# Prototipo_2X.net
KiCad netlist of a schematic drawn in EAGLE
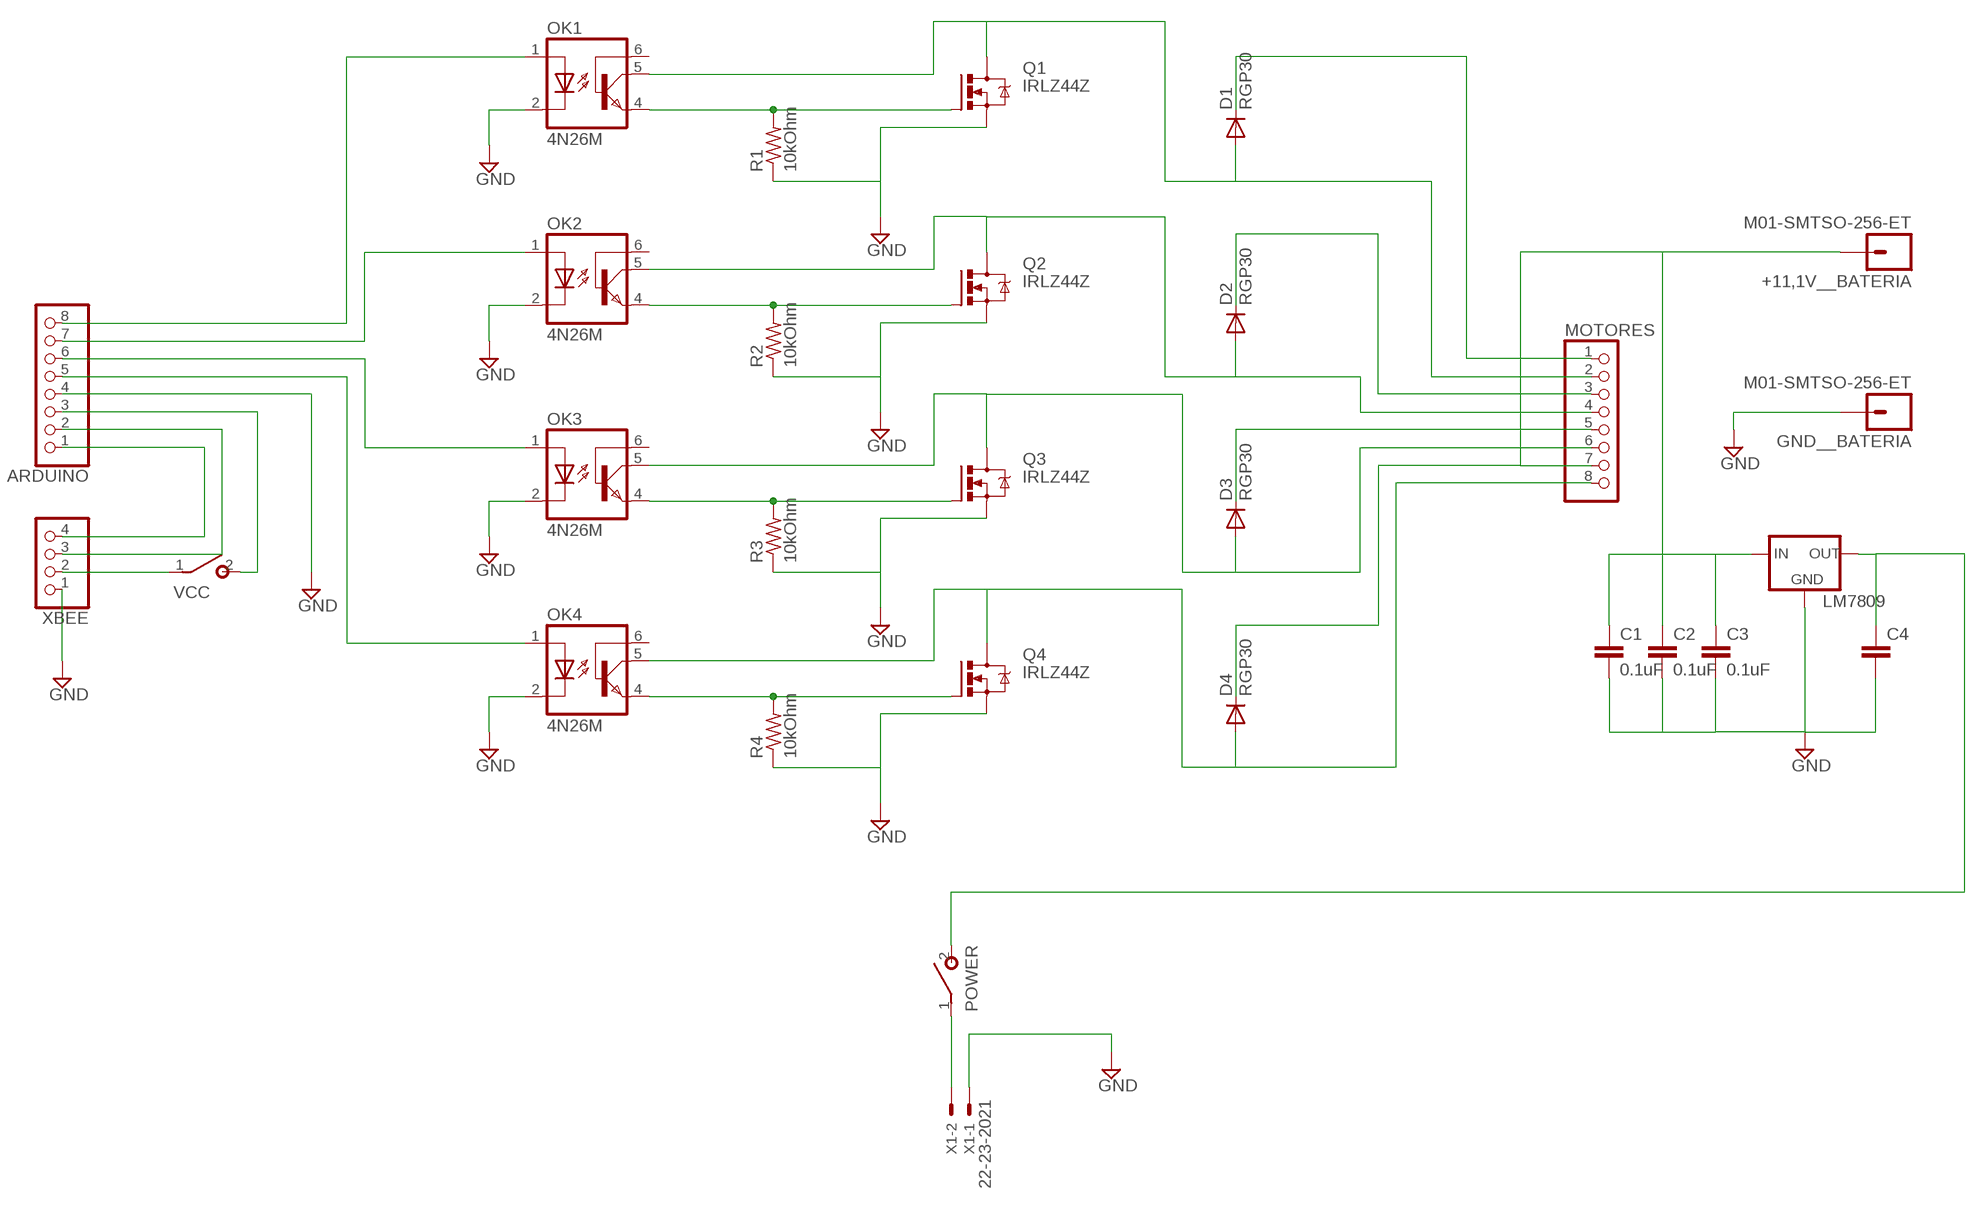
[diagram p0: schematic, sheet 1]

(export (version "E")
  (design (tool "Eeschema 10.0.6"))
  (components
    (comp (ref "+11,1V__BATERIA")
      (value "M01-SMTSO-256-ET")
      (footprint "eagle-import:SMTSO-256-ET")
      (libsource (lib "eagle-import") (part "M01-SMTSO-256-ET"))
    )
    (comp (ref "ARDUINO")
      (value "PINHD-1X8/90")
      (footprint "eagle-import:1X08_90")
      (libsource (lib "eagle-import") (part "PINHD-1X8/90"))
    )
    (comp (ref "C1")
      (value "0.1uF")
      (footprint "eagle-import:CAP-PTH-SMALL-KIT")
      (fields (field (name "PROD_ID") "CAP-08370"))
      (libsource (lib "eagle-import") (part "0.1UF-50V-20%(PTH)KIT-EZ"))
    )
    (comp (ref "C2")
      (value "0.1uF")
      (footprint "eagle-import:CAP-PTH-SMALL-KIT")
      (fields (field (name "PROD_ID") "CAP-08370"))
      (libsource (lib "eagle-import") (part "0.1UF-50V-20%(PTH)KIT-EZ"))
    )
    (comp (ref "C3")
      (value "0.1uF")
      (footprint "eagle-import:CAP-PTH-SMALL-KIT")
      (libsource (lib "eagle-import") (part "0.1UF-50V-20%(PTH)KIT-EZ"))
    )
    (comp (ref "C4")
      (value "0.1UF-50V-20%(PTH)KIT-EZ")
      (footprint "eagle-import:CAP-PTH-SMALL-KIT")
      (fields (field (name "PROD_ID") "CAP-08370"))
      (libsource (lib "eagle-import") (part "0.1UF-50V-20%(PTH)KIT-EZ"))
    )
    (comp (ref "D1")
      (value "RGP30")
      (footprint "eagle-import:DO201-15")
      (libsource (lib "eagle-import") (part "RGP30"))
    )
    (comp (ref "D2")
      (value "RGP30")
      (footprint "eagle-import:DO201-15")
      (libsource (lib "eagle-import") (part "RGP30"))
    )
    (comp (ref "D3")
      (value "RGP30")
      (footprint "eagle-import:DO201-15")
      (libsource (lib "eagle-import") (part "RGP30"))
    )
    (comp (ref "D4")
      (value "RGP30")
      (footprint "eagle-import:DO201-15")
      (libsource (lib "eagle-import") (part "RGP30"))
    )
    (comp (ref "GND__BATERIA")
      (value "M01-SMTSO-256-ET")
      (footprint "eagle-import:SMTSO-256-ET")
      (libsource (lib "eagle-import") (part "M01-SMTSO-256-ET"))
    )
    (comp (ref "LM7809")
      (value "78XXL")
      (footprint "eagle-import:78XXL")
      (libsource (lib "eagle-import") (part "78XXL"))
    )
    (comp (ref "MOTORES")
      (value "PINHD-1X8/90")
      (footprint "eagle-import:1X08_90")
      (libsource (lib "eagle-import") (part "PINHD-1X8/90"))
    )
    (comp (ref "OK1")
      (value "4N26M")
      (footprint "eagle-import:DIL06")
      (fields (field (name "MPN") "4N26-M"))
      (libsource (lib "eagle-import") (part "4N?M26"))
    )
    (comp (ref "OK2")
      (value "4N26M")
      (footprint "eagle-import:DIL06")
      (fields (field (name "MPN") "4N26-M"))
      (libsource (lib "eagle-import") (part "4N?M26"))
    )
    (comp (ref "OK3")
      (value "4N26M")
      (footprint "eagle-import:DIL06")
      (fields (field (name "MPN") "4N26-M"))
      (libsource (lib "eagle-import") (part "4N?M26"))
    )
    (comp (ref "OK4")
      (value "4N26M")
      (footprint "eagle-import:DIL06")
      (fields (field (name "MPN") "4N26-M"))
      (libsource (lib "eagle-import") (part "4N?M26"))
    )
    (comp (ref "POWER")
      (value "SPST")
      (footprint "eagle-import:SPST")
      (libsource (lib "eagle-import") (part "SPST"))
    )
    (comp (ref "Q1")
      (value "IRLZ44Z")
      (footprint "eagle-import:TO220BH")
      (libsource (lib "eagle-import") (part "IRLZ44Z"))
    )
    (comp (ref "Q2")
      (value "IRLZ44Z")
      (footprint "eagle-import:TO220BH")
      (libsource (lib "eagle-import") (part "IRLZ44Z"))
    )
    (comp (ref "Q3")
      (value "IRLZ44Z")
      (footprint "eagle-import:TO220BH")
      (libsource (lib "eagle-import") (part "IRLZ44Z"))
    )
    (comp (ref "Q4")
      (value "IRLZ44Z")
      (footprint "eagle-import:TO220BH")
      (libsource (lib "eagle-import") (part "IRLZ44Z"))
    )
    (comp (ref "R1")
      (value "10kOhm")
      (footprint "eagle-import:0207_7")
      (libsource (lib "eagle-import") (part "R-US_0207/7"))
    )
    (comp (ref "R2")
      (value "10kOhm")
      (footprint "eagle-import:0207_7")
      (libsource (lib "eagle-import") (part "R-US_0207/7"))
    )
    (comp (ref "R3")
      (value "10kOhm")
      (footprint "eagle-import:0207_7")
      (libsource (lib "eagle-import") (part "R-US_0207/7"))
    )
    (comp (ref "R4")
      (value "10kOhm")
      (footprint "eagle-import:0207_7")
      (libsource (lib "eagle-import") (part "R-US_0207/7"))
    )
    (comp (ref "VCC")
      (value "SPST")
      (footprint "eagle-import:SPST")
      (libsource (lib "eagle-import") (part "SPST"))
    )
    (comp (ref "X1")
      (value "22-23-2021")
      (footprint "eagle-import:22-23-2021")
      (fields (field (name "MF") "MOLEX"))
      (libsource (lib "eagle-import") (part "22-23-2021"))
    )
    (comp (ref "XBEE")
      (value "PINHD-1X4")
      (footprint "eagle-import:1X04")
      (libsource (lib "eagle-import") (part "PINHD-1X4"))
    )
  )
  (nets
    (net (code "1") (name "GND") (class "Default")
      (node (ref "ARDUINO") (pin "4") (pinfunction "4_4") (pintype "passive"))
      (node (ref "C1") (pin "2") (pinfunction "2_2") (pintype "passive"))
      (node (ref "C2") (pin "2") (pinfunction "2_2") (pintype "passive"))
      (node (ref "C3") (pin "2") (pinfunction "2_2") (pintype "passive"))
      (node (ref "C4") (pin "2") (pinfunction "2_2") (pintype "passive"))
      (node (ref "GND__BATERIA") (pin "P$1") (pinfunction "1_P$1") (pintype "passive"))
      (node (ref "LM7809") (pin "GND") (pinfunction "GND_GND") (pintype "input"))
      (node (ref "OK1") (pin "2") (pinfunction "C_2") (pintype "passive"))
      (node (ref "OK2") (pin "2") (pinfunction "C_2") (pintype "passive"))
      (node (ref "OK3") (pin "2") (pinfunction "C_2") (pintype "passive"))
      (node (ref "OK4") (pin "2") (pinfunction "C_2") (pintype "passive"))
      (node (ref "Q1") (pin "S") (pinfunction "S_S") (pintype "passive"))
      (node (ref "Q2") (pin "S") (pinfunction "S_S") (pintype "passive"))
      (node (ref "Q3") (pin "S") (pinfunction "S_S") (pintype "passive"))
      (node (ref "Q4") (pin "S") (pinfunction "S_S") (pintype "passive"))
      (node (ref "R1") (pin "1") (pinfunction "1_1") (pintype "passive"))
      (node (ref "R2") (pin "1") (pinfunction "1_1") (pintype "passive"))
      (node (ref "R3") (pin "1") (pinfunction "1_1") (pintype "passive"))
      (node (ref "R4") (pin "1") (pinfunction "1_1") (pintype "passive"))
      (node (ref "X1") (pin "1") (pinfunction "S_1") (pintype "passive"))
      (node (ref "XBEE") (pin "1") (pinfunction "1_1") (pintype "passive"))
    )
    (net (code "2") (name "Net-(+11,1V__BATERIA-1)") (class "Default")
      (node (ref "+11,1V__BATERIA") (pin "P$1") (pinfunction "1_P$1") (pintype "passive"))
      (node (ref "C1") (pin "1") (pinfunction "1_1") (pintype "passive"))
      (node (ref "C2") (pin "1") (pinfunction "1_1") (pintype "passive"))
      (node (ref "C3") (pin "1") (pinfunction "1_1") (pintype "passive"))
      (node (ref "D1") (pin "C") (pinfunction "C_C") (pintype "passive"))
      (node (ref "D2") (pin "C") (pinfunction "C_C") (pintype "passive"))
      (node (ref "D3") (pin "C") (pinfunction "C_C") (pintype "passive"))
      (node (ref "D4") (pin "C") (pinfunction "C_C") (pintype "passive"))
      (node (ref "LM7809") (pin "IN") (pinfunction "IN_IN") (pintype "input"))
      (node (ref "MOTORES") (pin "1") (pinfunction "1_1") (pintype "passive"))
      (node (ref "MOTORES") (pin "3") (pinfunction "3_3") (pintype "passive"))
      (node (ref "MOTORES") (pin "5") (pinfunction "5_5") (pintype "passive"))
      (node (ref "MOTORES") (pin "7") (pinfunction "7_7") (pintype "passive"))
    )
    (net (code "3") (name "Net-(ARDUINO-Pad1)") (class "Default")
      (node (ref "ARDUINO") (pin "1") (pinfunction "1_1") (pintype "passive"))
      (node (ref "XBEE") (pin "4") (pinfunction "4_4") (pintype "passive"))
    )
    (net (code "4") (name "Net-(ARDUINO-Pad2)") (class "Default")
      (node (ref "ARDUINO") (pin "2") (pinfunction "2_2") (pintype "passive"))
      (node (ref "XBEE") (pin "3") (pinfunction "3_3") (pintype "passive"))
    )
    (net (code "5") (name "Net-(OK1-A)") (class "Default")
      (node (ref "ARDUINO") (pin "8") (pinfunction "8_8") (pintype "passive"))
      (node (ref "OK1") (pin "1") (pinfunction "A_1") (pintype "passive"))
    )
    (net (code "6") (name "Net-(OK1-COL)") (class "Default")
      (node (ref "D1") (pin "A") (pinfunction "A_A") (pintype "passive"))
      (node (ref "MOTORES") (pin "2") (pinfunction "2_2") (pintype "passive"))
      (node (ref "OK1") (pin "5") (pinfunction "COL_5") (pintype "passive"))
      (node (ref "Q1") (pin "D") (pinfunction "D_D") (pintype "passive"))
    )
    (net (code "7") (name "Net-(OK1-EMI)") (class "Default")
      (node (ref "OK1") (pin "4") (pinfunction "EMI_4") (pintype "passive"))
      (node (ref "Q1") (pin "G") (pinfunction "G_G") (pintype "passive"))
      (node (ref "R1") (pin "2") (pinfunction "2_2") (pintype "passive"))
    )
    (net (code "8") (name "Net-(OK2-A)") (class "Default")
      (node (ref "ARDUINO") (pin "7") (pinfunction "7_7") (pintype "passive"))
      (node (ref "OK2") (pin "1") (pinfunction "A_1") (pintype "passive"))
    )
    (net (code "9") (name "Net-(OK2-COL)") (class "Default")
      (node (ref "D2") (pin "A") (pinfunction "A_A") (pintype "passive"))
      (node (ref "MOTORES") (pin "4") (pinfunction "4_4") (pintype "passive"))
      (node (ref "OK2") (pin "5") (pinfunction "COL_5") (pintype "passive"))
      (node (ref "Q2") (pin "D") (pinfunction "D_D") (pintype "passive"))
    )
    (net (code "10") (name "Net-(OK2-EMI)") (class "Default")
      (node (ref "OK2") (pin "4") (pinfunction "EMI_4") (pintype "passive"))
      (node (ref "Q2") (pin "G") (pinfunction "G_G") (pintype "passive"))
      (node (ref "R2") (pin "2") (pinfunction "2_2") (pintype "passive"))
    )
    (net (code "11") (name "Net-(OK3-A)") (class "Default")
      (node (ref "ARDUINO") (pin "6") (pinfunction "6_6") (pintype "passive"))
      (node (ref "OK3") (pin "1") (pinfunction "A_1") (pintype "passive"))
    )
    (net (code "12") (name "Net-(OK3-COL)") (class "Default")
      (node (ref "D3") (pin "A") (pinfunction "A_A") (pintype "passive"))
      (node (ref "MOTORES") (pin "6") (pinfunction "6_6") (pintype "passive"))
      (node (ref "OK3") (pin "5") (pinfunction "COL_5") (pintype "passive"))
      (node (ref "Q3") (pin "D") (pinfunction "D_D") (pintype "passive"))
    )
    (net (code "13") (name "Net-(OK3-EMI)") (class "Default")
      (node (ref "OK3") (pin "4") (pinfunction "EMI_4") (pintype "passive"))
      (node (ref "Q3") (pin "G") (pinfunction "G_G") (pintype "passive"))
      (node (ref "R3") (pin "2") (pinfunction "2_2") (pintype "passive"))
    )
    (net (code "14") (name "Net-(OK4-A)") (class "Default")
      (node (ref "ARDUINO") (pin "5") (pinfunction "5_5") (pintype "passive"))
      (node (ref "OK4") (pin "1") (pinfunction "A_1") (pintype "passive"))
    )
    (net (code "15") (name "Net-(OK4-COL)") (class "Default")
      (node (ref "D4") (pin "A") (pinfunction "A_A") (pintype "passive"))
      (node (ref "MOTORES") (pin "8") (pinfunction "8_8") (pintype "passive"))
      (node (ref "OK4") (pin "5") (pinfunction "COL_5") (pintype "passive"))
      (node (ref "Q4") (pin "D") (pinfunction "D_D") (pintype "passive"))
    )
    (net (code "16") (name "Net-(OK4-EMI)") (class "Default")
      (node (ref "OK4") (pin "4") (pinfunction "EMI_4") (pintype "passive"))
      (node (ref "Q4") (pin "G") (pinfunction "G_G") (pintype "passive"))
      (node (ref "R4") (pin "2") (pinfunction "2_2") (pintype "passive"))
    )
    (net (code "17") (name "Net-(POWER-P)") (class "Default")
      (node (ref "POWER") (pin "1") (pinfunction "P_1") (pintype "passive"))
      (node (ref "X1") (pin "2") (pinfunction "S_2") (pintype "passive"))
    )
    (net (code "18") (name "Net-(POWER-S)") (class "Default")
      (node (ref "C4") (pin "1") (pinfunction "1_1") (pintype "passive"))
      (node (ref "LM7809") (pin "OUT") (pinfunction "OUT_OUT") (pintype "passive"))
      (node (ref "POWER") (pin "2") (pinfunction "S_2") (pintype "passive"))
    )
    (net (code "19") (name "Net-(VCC-P)") (class "Default")
      (node (ref "VCC") (pin "1") (pinfunction "P_1") (pintype "passive"))
      (node (ref "XBEE") (pin "2") (pinfunction "2_2") (pintype "passive"))
    )
    (net (code "20") (name "Net-(VCC-S)") (class "Default")
      (node (ref "ARDUINO") (pin "3") (pinfunction "3_3") (pintype "passive"))
      (node (ref "VCC") (pin "2") (pinfunction "S_2") (pintype "passive"))
    )
    (net (code "21") (name "unconnected-(OK1-BAS-Pad6)") (class "Default")
      (node (ref "OK1") (pin "6") (pinfunction "BAS_6") (pintype "passive"))
    )
    (net (code "22") (name "unconnected-(OK2-BAS-Pad6)") (class "Default")
      (node (ref "OK2") (pin "6") (pinfunction "BAS_6") (pintype "passive"))
    )
    (net (code "23") (name "unconnected-(OK3-BAS-Pad6)") (class "Default")
      (node (ref "OK3") (pin "6") (pinfunction "BAS_6") (pintype "passive"))
    )
    (net (code "24") (name "unconnected-(OK4-BAS-Pad6)") (class "Default")
      (node (ref "OK4") (pin "6") (pinfunction "BAS_6") (pintype "passive"))
    )
  )
)
